# 6_RGBLED.net
KiCad netlist of a schematic drawn in Altium Designer
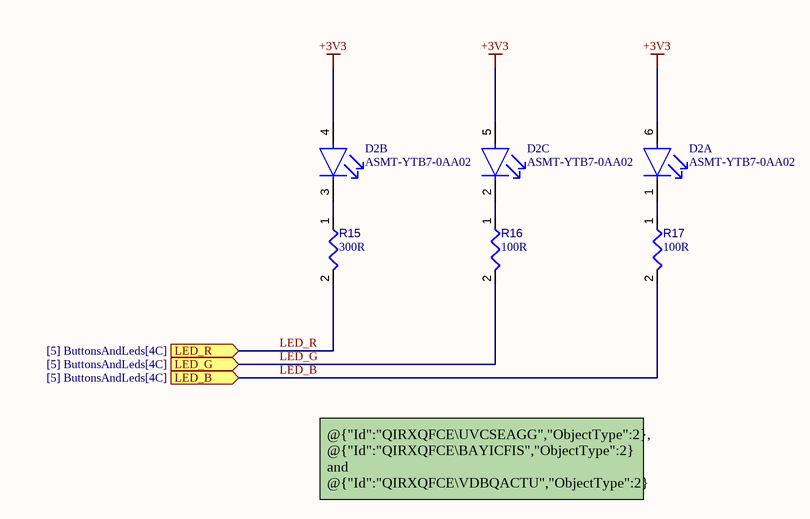
[diagram p0: [6] RGBLED.SchDoc]

(export (version "E")
  (design (tool "Eeschema 10.0.6"))
  (components
    (comp (ref "D2")
      (value "ASMT-YTB7-0AA02")
      (footprint "FP-PLCC-6-MFG")
      (description "LED Tri-Color Blue/Green/Red 469nm/529nm/623nm Chip LED 6-Pin PLCC T/R")
      (libsource (lib "UFCG - Universidade Federal de Campina Grande") (part "0f3d36aaa98356051a15b42400af8f3"))
    )
    (comp (ref "R15")
      (value "300R")
      (footprint "RESC0603(1608)_L")
      (description "Res Thick Film 0603 300 Ohm 5% 1/10W ±200ppm/°C Molded SMD Punched Carrier T/R")
      (fields (field (name "TOLERANCE") "5%") (field (name "Comment") "ERJ-3GEYJ301V"))
      (libsource (lib "UFCG - Universidade Federal de Campina Grande") (part "RES-2"))
    )
    (comp (ref "R16")
      (value "100R")
      (footprint "RESC0603(1608)_L")
      (description "SMD Chip Resistor, 100 Ohm, ï¿½ 1%, 100 mW, 0603 [1608 Metric], Thick Film, Precision")
      (fields (field (name "TOLERANCE") "1%") (field (name "Comment") "ERJ-3EKF1000V"))
      (libsource (lib "UFCG - Universidade Federal de Campina Grande") (part "RES-2"))
    )
    (comp (ref "R17")
      (value "100R")
      (footprint "RESC0603(1608)_L")
      (description "SMD Chip Resistor, 100 Ohm, ï¿½ 1%, 100 mW, 0603 [1608 Metric], Thick Film, Precision")
      (fields (field (name "TOLERANCE") "1%") (field (name "Comment") "ERJ-3EKF1000V"))
      (libsource (lib "UFCG - Universidade Federal de Campina Grande") (part "RES-2"))
    )
  )
  (nets
    (net (code "1") (name "+3V3") (class "Default")
      (node (ref "D2") (pin "4") (pinfunction "Anode(Red)_4") (pintype "passive"))
      (node (ref "D2") (pin "5") (pinfunction "Anode(Green)_5") (pintype "passive"))
      (node (ref "D2") (pin "6") (pinfunction "Anode(Blue)_6") (pintype "passive"))
    )
    (net (code "2") (name "/LED_B") (class "Default")
      (node (ref "R17") (pin "2") (pinfunction "2_2") (pintype "passive"))
    )
    (net (code "3") (name "/LED_G") (class "Default")
      (node (ref "R16") (pin "2") (pinfunction "2_2") (pintype "passive"))
    )
    (net (code "4") (name "/LED_R") (class "Default")
      (node (ref "R15") (pin "2") (pinfunction "2_2") (pintype "passive"))
    )
    (net (code "5") (name "Net-(D2A-Cathode(Blue))") (class "Default")
      (node (ref "D2") (pin "1") (pinfunction "Cathode(Blue)_1") (pintype "passive"))
      (node (ref "R17") (pin "1") (pinfunction "1_1") (pintype "passive"))
    )
    (net (code "6") (name "Net-(D2B-Cathode(Red))") (class "Default")
      (node (ref "D2") (pin "3") (pinfunction "Cathode(Red)_3") (pintype "passive"))
      (node (ref "R15") (pin "1") (pinfunction "1_1") (pintype "passive"))
    )
    (net (code "7") (name "Net-(D2C-Cathode(Green))") (class "Default")
      (node (ref "D2") (pin "2") (pinfunction "Cathode(Green)_2") (pintype "passive"))
      (node (ref "R16") (pin "1") (pinfunction "1_1") (pintype "passive"))
    )
  )
)
